# Arbolito.net
KiCad netlist of a schematic drawn in Altium Designer
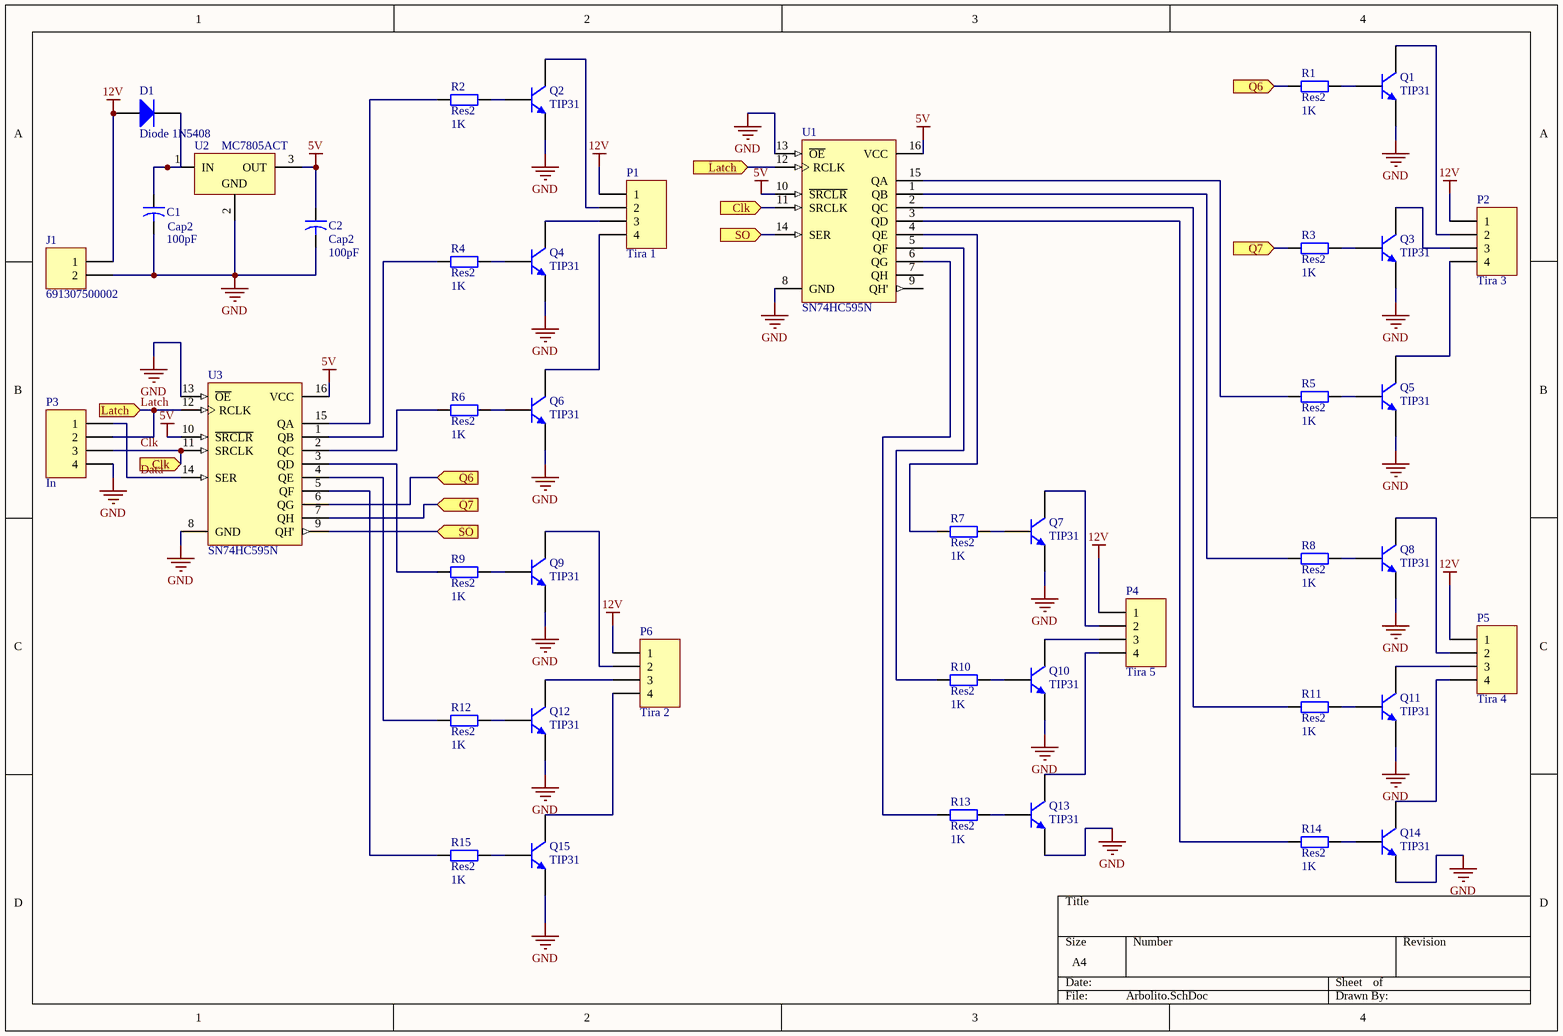
[diagram p0: Arbolito.SchDoc]

(export (version "E")
  (design (tool "Eeschema 10.0.6"))
  (components
    (comp (ref "C1")
      (value "Cap2")
      (footprint "CAPR5-4X5")
      (description "Capacitor")
      (fields (field (name "ALTIUM_VALUE") "100pF") (field (name "PUBLISHER") "Altium Limited"))
      (libsource (lib "Miscellaneous Devices") (part "Cap2"))
    )
    (comp (ref "C2")
      (value "Cap2")
      (footprint "CAPR5-4X5")
      (description "Capacitor")
      (fields (field (name "ALTIUM_VALUE") "100pF") (field (name "PUBLISHER") "Altium Limited"))
      (libsource (lib "Miscellaneous Devices") (part "Cap2"))
    )
    (comp (ref "D1")
      (value "Diode 1N5408")
      (footprint "DO-201AD")
      (description "3 Amp Medium Power Silicon Rectifier Diode")
      (fields (field (name "PUBLISHER") "Altium Limited"))
      (libsource (lib "Miscellaneous Devices") (part "Diode 1N5408"))
    )
    (comp (ref "J1")
      (value "691307500002")
      (footprint "691307500002")
      (description "WR-TBL Terminal block - serie 3075")
      (fields
        (field (name "MANUFACTURER") "Würth Elektronik eiSos GmbH")
        (field (name "CREATED BY") "Karrer Zheng")
      )
      (libsource (lib "WE_WR-TBL_Pluggable System_5.08 mm_rev15b") (part "691307500002"))
    )
    (comp (ref "P1")
      (value "Tira 1")
      (footprint "HDR1X4")
      (description "Header, 4-Pin")
      (fields (field (name "PUBLISHER") "Altium Limited"))
      (libsource (lib "Miscellaneous Connectors") (part "Header 4"))
    )
    (comp (ref "P2")
      (value "Tira 3")
      (footprint "HDR1X4")
      (description "Header, 4-Pin")
      (fields (field (name "PUBLISHER") "Altium Limited"))
      (libsource (lib "Miscellaneous Connectors") (part "Header 4"))
    )
    (comp (ref "P3")
      (value "In")
      (footprint "HDR1X4")
      (description "Header, 4-Pin")
      (fields (field (name "PUBLISHER") "Altium Limited"))
      (libsource (lib "") (part "Header 4_1"))
    )
    (comp (ref "P4")
      (value "Tira 5")
      (footprint "HDR1X4")
      (description "Header, 4-Pin")
      (fields (field (name "PUBLISHER") "Altium Limited"))
      (libsource (lib "Miscellaneous Connectors") (part "Header 4"))
    )
    (comp (ref "P5")
      (value "Tira 4")
      (footprint "HDR1X4")
      (description "Header, 4-Pin")
      (fields (field (name "PUBLISHER") "Altium Limited"))
      (libsource (lib "Miscellaneous Connectors") (part "Header 4"))
    )
    (comp (ref "P6")
      (value "Tira 2")
      (footprint "HDR1X4")
      (description "Header, 4-Pin")
      (fields (field (name "PUBLISHER") "Altium Limited"))
      (libsource (lib "Miscellaneous Connectors") (part "Header 4"))
    )
    (comp (ref "Q1")
      (value "TIP31")
      (footprint "TO-220-AB")
      (description "NPN General Purpose Amplifier")
      (fields (field (name "PUBLISHER") "Altium Limited"))
      (libsource (lib "Miscellaneous Devices") (part "2N3904"))
    )
    (comp (ref "Q2")
      (value "TIP31")
      (footprint "TO-220-AB")
      (description "NPN General Purpose Amplifier")
      (fields (field (name "PUBLISHER") "Altium Limited"))
      (libsource (lib "Miscellaneous Devices") (part "2N3904"))
    )
    (comp (ref "Q3")
      (value "TIP31")
      (footprint "TO-220-AB")
      (description "NPN General Purpose Amplifier")
      (fields (field (name "PUBLISHER") "Altium Limited"))
      (libsource (lib "Miscellaneous Devices") (part "2N3904"))
    )
    (comp (ref "Q4")
      (value "TIP31")
      (footprint "TO-220-AB")
      (description "NPN General Purpose Amplifier")
      (fields (field (name "PUBLISHER") "Altium Limited"))
      (libsource (lib "Miscellaneous Devices") (part "2N3904"))
    )
    (comp (ref "Q5")
      (value "TIP31")
      (footprint "TO-220-AB")
      (description "NPN General Purpose Amplifier")
      (fields (field (name "PUBLISHER") "Altium Limited"))
      (libsource (lib "Miscellaneous Devices") (part "2N3904"))
    )
    (comp (ref "Q6")
      (value "TIP31")
      (footprint "TO-220-AB")
      (description "NPN General Purpose Amplifier")
      (fields (field (name "PUBLISHER") "Altium Limited"))
      (libsource (lib "Miscellaneous Devices") (part "2N3904"))
    )
    (comp (ref "Q7")
      (value "TIP31")
      (footprint "TO-220-AB")
      (description "NPN General Purpose Amplifier")
      (fields (field (name "PUBLISHER") "Altium Limited"))
      (libsource (lib "Miscellaneous Devices") (part "2N3904"))
    )
    (comp (ref "Q8")
      (value "TIP31")
      (footprint "TO-220-AB")
      (description "NPN General Purpose Amplifier")
      (fields (field (name "PUBLISHER") "Altium Limited"))
      (libsource (lib "Miscellaneous Devices") (part "2N3904"))
    )
    (comp (ref "Q9")
      (value "TIP31")
      (footprint "TO-220-AB")
      (description "NPN General Purpose Amplifier")
      (fields (field (name "PUBLISHER") "Altium Limited"))
      (libsource (lib "Miscellaneous Devices") (part "2N3904"))
    )
    (comp (ref "Q10")
      (value "TIP31")
      (footprint "TO-220-AB")
      (description "NPN General Purpose Amplifier")
      (fields (field (name "PUBLISHER") "Altium Limited"))
      (libsource (lib "Miscellaneous Devices") (part "2N3904"))
    )
    (comp (ref "Q11")
      (value "TIP31")
      (footprint "TO-220-AB")
      (description "NPN General Purpose Amplifier")
      (fields (field (name "PUBLISHER") "Altium Limited"))
      (libsource (lib "Miscellaneous Devices") (part "2N3904"))
    )
    (comp (ref "Q12")
      (value "TIP31")
      (footprint "TO-220-AB")
      (description "NPN General Purpose Amplifier")
      (fields (field (name "PUBLISHER") "Altium Limited"))
      (libsource (lib "Miscellaneous Devices") (part "2N3904"))
    )
    (comp (ref "Q13")
      (value "TIP31")
      (footprint "TO-220-AB")
      (description "NPN General Purpose Amplifier")
      (fields (field (name "PUBLISHER") "Altium Limited"))
      (libsource (lib "Miscellaneous Devices") (part "2N3904"))
    )
    (comp (ref "Q14")
      (value "TIP31")
      (footprint "TO-220-AB")
      (description "NPN General Purpose Amplifier")
      (fields (field (name "PUBLISHER") "Altium Limited"))
      (libsource (lib "Miscellaneous Devices") (part "2N3904"))
    )
    (comp (ref "Q15")
      (value "TIP31")
      (footprint "TO-220-AB")
      (description "NPN General Purpose Amplifier")
      (fields (field (name "PUBLISHER") "Altium Limited"))
      (libsource (lib "Miscellaneous Devices") (part "2N3904"))
    )
    (comp (ref "R1")
      (value "Res2")
      (footprint "AXIAL-0.4")
      (description "Resistor")
      (fields (field (name "ALTIUM_VALUE") "1K") (field (name "PUBLISHER") "Altium Limited"))
      (libsource (lib "Miscellaneous Devices") (part "Res2"))
    )
    (comp (ref "R2")
      (value "Res2")
      (footprint "AXIAL-0.4")
      (description "Resistor")
      (fields (field (name "ALTIUM_VALUE") "1K") (field (name "PUBLISHER") "Altium Limited"))
      (libsource (lib "Miscellaneous Devices") (part "Res2"))
    )
    (comp (ref "R3")
      (value "Res2")
      (footprint "AXIAL-0.4")
      (description "Resistor")
      (fields (field (name "ALTIUM_VALUE") "1K") (field (name "PUBLISHER") "Altium Limited"))
      (libsource (lib "Miscellaneous Devices") (part "Res2"))
    )
    (comp (ref "R4")
      (value "Res2")
      (footprint "AXIAL-0.4")
      (description "Resistor")
      (fields (field (name "ALTIUM_VALUE") "1K") (field (name "PUBLISHER") "Altium Limited"))
      (libsource (lib "Miscellaneous Devices") (part "Res2"))
    )
    (comp (ref "R5")
      (value "Res2")
      (footprint "AXIAL-0.4")
      (description "Resistor")
      (fields (field (name "ALTIUM_VALUE") "1K") (field (name "PUBLISHER") "Altium Limited"))
      (libsource (lib "Miscellaneous Devices") (part "Res2"))
    )
    (comp (ref "R6")
      (value "Res2")
      (footprint "AXIAL-0.4")
      (description "Resistor")
      (fields (field (name "ALTIUM_VALUE") "1K") (field (name "PUBLISHER") "Altium Limited"))
      (libsource (lib "Miscellaneous Devices") (part "Res2"))
    )
    (comp (ref "R7")
      (value "Res2")
      (footprint "AXIAL-0.4")
      (description "Resistor")
      (fields (field (name "ALTIUM_VALUE") "1K") (field (name "PUBLISHER") "Altium Limited"))
      (libsource (lib "Miscellaneous Devices") (part "Res2"))
    )
    (comp (ref "R8")
      (value "Res2")
      (footprint "AXIAL-0.4")
      (description "Resistor")
      (fields (field (name "ALTIUM_VALUE") "1K") (field (name "PUBLISHER") "Altium Limited"))
      (libsource (lib "Miscellaneous Devices") (part "Res2"))
    )
    (comp (ref "R9")
      (value "Res2")
      (footprint "AXIAL-0.4")
      (description "Resistor")
      (fields (field (name "ALTIUM_VALUE") "1K") (field (name "PUBLISHER") "Altium Limited"))
      (libsource (lib "Miscellaneous Devices") (part "Res2"))
    )
    (comp (ref "R10")
      (value "Res2")
      (footprint "AXIAL-0.4")
      (description "Resistor")
      (fields (field (name "ALTIUM_VALUE") "1K") (field (name "PUBLISHER") "Altium Limited"))
      (libsource (lib "Miscellaneous Devices") (part "Res2"))
    )
    (comp (ref "R11")
      (value "Res2")
      (footprint "AXIAL-0.4")
      (description "Resistor")
      (fields (field (name "ALTIUM_VALUE") "1K") (field (name "PUBLISHER") "Altium Limited"))
      (libsource (lib "Miscellaneous Devices") (part "Res2"))
    )
    (comp (ref "R12")
      (value "Res2")
      (footprint "AXIAL-0.4")
      (description "Resistor")
      (fields (field (name "ALTIUM_VALUE") "1K") (field (name "PUBLISHER") "Altium Limited"))
      (libsource (lib "Miscellaneous Devices") (part "Res2"))
    )
    (comp (ref "R13")
      (value "Res2")
      (footprint "AXIAL-0.4")
      (description "Resistor")
      (fields (field (name "ALTIUM_VALUE") "1K") (field (name "PUBLISHER") "Altium Limited"))
      (libsource (lib "Miscellaneous Devices") (part "Res2"))
    )
    (comp (ref "R14")
      (value "Res2")
      (footprint "AXIAL-0.4")
      (description "Resistor")
      (fields (field (name "ALTIUM_VALUE") "1K") (field (name "PUBLISHER") "Altium Limited"))
      (libsource (lib "Miscellaneous Devices") (part "Res2"))
    )
    (comp (ref "R15")
      (value "Res2")
      (footprint "AXIAL-0.4")
      (description "Resistor")
      (fields (field (name "ALTIUM_VALUE") "1K") (field (name "PUBLISHER") "Altium Limited"))
      (libsource (lib "Miscellaneous Devices") (part "Res2"))
    )
    (comp (ref "U1")
      (value "SN74HC595N")
      (footprint "N016")
      (description "8-Bit Shift Register with 3-State Output Registers")
      (fields (field (name "PUBLISHER") "Altium Limited"))
      (libsource (lib "TI Logic Register") (part "SN74HC595N"))
    )
    (comp (ref "U2")
      (value "MC7805ACT")
      (footprint "221A-04")
      (description "3-Terminal Positive Fixed Voltage Regulator")
      (fields (field (name "PUBLISHER") "Altium Limited"))
      (libsource (lib "Motorola Power Mgt Voltage Regulator") (part "MC7805ACT"))
    )
    (comp (ref "U3")
      (value "SN74HC595N")
      (footprint "N016")
      (description "8-Bit Shift Register with 3-State Output Registers")
      (fields (field (name "PUBLISHER") "Altium Limited"))
      (libsource (lib "TI Logic Register") (part "SN74HC595N"))
    )
  )
  (nets
    (net (code "1") (name "/Clk") (class "Default")
      (node (ref "P3") (pin "3") (pinfunction "3_3") (pintype "passive"))
      (node (ref "U1") (pin "11") (pinfunction "SRCLK_11") (pintype "input"))
      (node (ref "U3") (pin "11") (pinfunction "SRCLK_11") (pintype "input"))
    )
    (net (code "2") (name "/Data") (class "Default")
      (node (ref "P3") (pin "1") (pinfunction "1_1") (pintype "passive"))
      (node (ref "U3") (pin "14") (pinfunction "SER_14") (pintype "input"))
    )
    (net (code "3") (name "/Latch") (class "Default")
      (node (ref "P3") (pin "2") (pinfunction "2_2") (pintype "passive"))
      (node (ref "U1") (pin "12") (pinfunction "RCLK_12") (pintype "input"))
      (node (ref "U3") (pin "12") (pinfunction "RCLK_12") (pintype "input"))
    )
    (net (code "4") (name "/Q6") (class "Default")
      (node (ref "R1") (pin "1") (pinfunction "1_1") (pintype "passive"))
      (node (ref "U3") (pin "6") (pinfunction "QG_6") (pintype "tri_state"))
    )
    (net (code "5") (name "/Q7") (class "Default")
      (node (ref "R3") (pin "1") (pinfunction "1_1") (pintype "passive"))
      (node (ref "U3") (pin "7") (pinfunction "QH_7") (pintype "tri_state"))
    )
    (net (code "6") (name "/SO") (class "Default")
      (node (ref "U1") (pin "14") (pinfunction "SER_14") (pintype "input"))
      (node (ref "U3") (pin "9") (pinfunction "QH'_9") (pintype "output"))
    )
    (net (code "7") (name "5V") (class "Default")
      (node (ref "C2") (pin "1") (pinfunction "1_1") (pintype "passive"))
      (node (ref "U1") (pin "10") (pinfunction "~{SRCLR}_10") (pintype "input"))
      (node (ref "U1") (pin "16") (pinfunction "VCC_16") (pintype "power_in"))
      (node (ref "U2") (pin "3") (pinfunction "OUT_3") (pintype "power_in"))
      (node (ref "U3") (pin "10") (pinfunction "~{SRCLR}_10") (pintype "input"))
      (node (ref "U3") (pin "16") (pinfunction "VCC_16") (pintype "power_in"))
    )
    (net (code "8") (name "12V") (class "Default")
      (node (ref "D1") (pin "1") (pinfunction "A_1") (pintype "passive"))
      (node (ref "J1") (pin "1") (pinfunction "1_1") (pintype "passive"))
      (node (ref "P1") (pin "1") (pinfunction "1_1") (pintype "passive"))
      (node (ref "P2") (pin "1") (pinfunction "1_1") (pintype "passive"))
      (node (ref "P4") (pin "1") (pinfunction "1_1") (pintype "passive"))
      (node (ref "P5") (pin "1") (pinfunction "1_1") (pintype "passive"))
      (node (ref "P6") (pin "1") (pinfunction "1_1") (pintype "passive"))
    )
    (net (code "9") (name "GND") (class "Default")
      (node (ref "C1") (pin "2") (pinfunction "2_2") (pintype "passive"))
      (node (ref "C2") (pin "2") (pinfunction "2_2") (pintype "passive"))
      (node (ref "J1") (pin "2") (pinfunction "2_2") (pintype "passive"))
      (node (ref "P3") (pin "4") (pinfunction "4_4") (pintype "passive"))
      (node (ref "Q1") (pin "1") (pinfunction "E_1") (pintype "passive"))
      (node (ref "Q10") (pin "1") (pinfunction "E_1") (pintype "passive"))
      (node (ref "Q11") (pin "1") (pinfunction "E_1") (pintype "passive"))
      (node (ref "Q12") (pin "1") (pinfunction "E_1") (pintype "passive"))
      (node (ref "Q13") (pin "1") (pinfunction "E_1") (pintype "passive"))
      (node (ref "Q14") (pin "1") (pinfunction "E_1") (pintype "passive"))
      (node (ref "Q15") (pin "1") (pinfunction "E_1") (pintype "passive"))
      (node (ref "Q2") (pin "1") (pinfunction "E_1") (pintype "passive"))
      (node (ref "Q3") (pin "1") (pinfunction "E_1") (pintype "passive"))
      (node (ref "Q4") (pin "1") (pinfunction "E_1") (pintype "passive"))
      (node (ref "Q5") (pin "1") (pinfunction "E_1") (pintype "passive"))
      (node (ref "Q6") (pin "1") (pinfunction "E_1") (pintype "passive"))
      (node (ref "Q7") (pin "1") (pinfunction "E_1") (pintype "passive"))
      (node (ref "Q8") (pin "1") (pinfunction "E_1") (pintype "passive"))
      (node (ref "Q9") (pin "1") (pinfunction "E_1") (pintype "passive"))
      (node (ref "U1") (pin "13") (pinfunction "~{OE}_13") (pintype "input"))
      (node (ref "U1") (pin "8") (pinfunction "GND_8") (pintype "power_in"))
      (node (ref "U2") (pin "2") (pinfunction "GND_2") (pintype "power_in"))
      (node (ref "U3") (pin "13") (pinfunction "~{OE}_13") (pintype "input"))
      (node (ref "U3") (pin "8") (pinfunction "GND_8") (pintype "power_in"))
    )
    (net (code "10") (name "Net-(D1-K)") (class "Default")
      (node (ref "C1") (pin "1") (pinfunction "1_1") (pintype "passive"))
      (node (ref "D1") (pin "2") (pinfunction "K_2") (pintype "passive"))
      (node (ref "U2") (pin "1") (pinfunction "IN_1") (pintype "power_in"))
    )
    (net (code "11") (name "Net-(Q1-B)") (class "Default")
      (node (ref "Q1") (pin "2") (pinfunction "B_2") (pintype "passive"))
      (node (ref "R1") (pin "2") (pinfunction "2_2") (pintype "passive"))
    )
    (net (code "12") (name "Net-(Q1-C)") (class "Default")
      (node (ref "P2") (pin "2") (pinfunction "2_2") (pintype "passive"))
      (node (ref "Q1") (pin "3") (pinfunction "C_3") (pintype "passive"))
    )
    (net (code "13") (name "Net-(Q2-B)") (class "Default")
      (node (ref "Q2") (pin "2") (pinfunction "B_2") (pintype "passive"))
      (node (ref "R2") (pin "2") (pinfunction "2_2") (pintype "passive"))
    )
    (net (code "14") (name "Net-(Q2-C)") (class "Default")
      (node (ref "P1") (pin "2") (pinfunction "2_2") (pintype "passive"))
      (node (ref "Q2") (pin "3") (pinfunction "C_3") (pintype "passive"))
    )
    (net (code "15") (name "Net-(Q3-B)") (class "Default")
      (node (ref "Q3") (pin "2") (pinfunction "B_2") (pintype "passive"))
      (node (ref "R3") (pin "2") (pinfunction "2_2") (pintype "passive"))
    )
    (net (code "16") (name "Net-(Q3-C)") (class "Default")
      (node (ref "P2") (pin "3") (pinfunction "3_3") (pintype "passive"))
      (node (ref "Q3") (pin "3") (pinfunction "C_3") (pintype "passive"))
    )
    (net (code "17") (name "Net-(Q4-B)") (class "Default")
      (node (ref "Q4") (pin "2") (pinfunction "B_2") (pintype "passive"))
      (node (ref "R4") (pin "2") (pinfunction "2_2") (pintype "passive"))
    )
    (net (code "18") (name "Net-(Q4-C)") (class "Default")
      (node (ref "P1") (pin "3") (pinfunction "3_3") (pintype "passive"))
      (node (ref "Q4") (pin "3") (pinfunction "C_3") (pintype "passive"))
    )
    (net (code "19") (name "Net-(Q5-B)") (class "Default")
      (node (ref "Q5") (pin "2") (pinfunction "B_2") (pintype "passive"))
      (node (ref "R5") (pin "2") (pinfunction "2_2") (pintype "passive"))
    )
    (net (code "20") (name "Net-(Q5-C)") (class "Default")
      (node (ref "P2") (pin "4") (pinfunction "4_4") (pintype "passive"))
      (node (ref "Q5") (pin "3") (pinfunction "C_3") (pintype "passive"))
    )
    (net (code "21") (name "Net-(Q6-B)") (class "Default")
      (node (ref "Q6") (pin "2") (pinfunction "B_2") (pintype "passive"))
      (node (ref "R6") (pin "2") (pinfunction "2_2") (pintype "passive"))
    )
    (net (code "22") (name "Net-(Q6-C)") (class "Default")
      (node (ref "P1") (pin "4") (pinfunction "4_4") (pintype "passive"))
      (node (ref "Q6") (pin "3") (pinfunction "C_3") (pintype "passive"))
    )
    (net (code "23") (name "Net-(Q7-B)") (class "Default")
      (node (ref "Q7") (pin "2") (pinfunction "B_2") (pintype "passive"))
      (node (ref "R7") (pin "2") (pinfunction "2_2") (pintype "passive"))
    )
    (net (code "24") (name "Net-(Q7-C)") (class "Default")
      (node (ref "P4") (pin "2") (pinfunction "2_2") (pintype "passive"))
      (node (ref "Q7") (pin "3") (pinfunction "C_3") (pintype "passive"))
    )
    (net (code "25") (name "Net-(Q8-B)") (class "Default")
      (node (ref "Q8") (pin "2") (pinfunction "B_2") (pintype "passive"))
      (node (ref "R8") (pin "2") (pinfunction "2_2") (pintype "passive"))
    )
    (net (code "26") (name "Net-(Q8-C)") (class "Default")
      (node (ref "P5") (pin "2") (pinfunction "2_2") (pintype "passive"))
      (node (ref "Q8") (pin "3") (pinfunction "C_3") (pintype "passive"))
    )
    (net (code "27") (name "Net-(Q9-B)") (class "Default")
      (node (ref "Q9") (pin "2") (pinfunction "B_2") (pintype "passive"))
      (node (ref "R9") (pin "2") (pinfunction "2_2") (pintype "passive"))
    )
    (net (code "28") (name "Net-(Q9-C)") (class "Default")
      (node (ref "P6") (pin "2") (pinfunction "2_2") (pintype "passive"))
      (node (ref "Q9") (pin "3") (pinfunction "C_3") (pintype "passive"))
    )
    (net (code "29") (name "Net-(Q10-B)") (class "Default")
      (node (ref "Q10") (pin "2") (pinfunction "B_2") (pintype "passive"))
      (node (ref "R10") (pin "2") (pinfunction "2_2") (pintype "passive"))
    )
    (net (code "30") (name "Net-(Q10-C)") (class "Default")
      (node (ref "P4") (pin "3") (pinfunction "3_3") (pintype "passive"))
      (node (ref "Q10") (pin "3") (pinfunction "C_3") (pintype "passive"))
    )
    (net (code "31") (name "Net-(Q11-B)") (class "Default")
      (node (ref "Q11") (pin "2") (pinfunction "B_2") (pintype "passive"))
      (node (ref "R11") (pin "2") (pinfunction "2_2") (pintype "passive"))
    )
    (net (code "32") (name "Net-(Q11-C)") (class "Default")
      (node (ref "P5") (pin "3") (pinfunction "3_3") (pintype "passive"))
      (node (ref "Q11") (pin "3") (pinfunction "C_3") (pintype "passive"))
    )
    (net (code "33") (name "Net-(Q12-B)") (class "Default")
      (node (ref "Q12") (pin "2") (pinfunction "B_2") (pintype "passive"))
      (node (ref "R12") (pin "2") (pinfunction "2_2") (pintype "passive"))
    )
    (net (code "34") (name "Net-(Q12-C)") (class "Default")
      (node (ref "P6") (pin "3") (pinfunction "3_3") (pintype "passive"))
      (node (ref "Q12") (pin "3") (pinfunction "C_3") (pintype "passive"))
    )
    (net (code "35") (name "Net-(Q13-B)") (class "Default")
      (node (ref "Q13") (pin "2") (pinfunction "B_2") (pintype "passive"))
      (node (ref "R13") (pin "2") (pinfunction "2_2") (pintype "passive"))
    )
    (net (code "36") (name "Net-(Q13-C)") (class "Default")
      (node (ref "P4") (pin "4") (pinfunction "4_4") (pintype "passive"))
      (node (ref "Q13") (pin "3") (pinfunction "C_3") (pintype "passive"))
    )
    (net (code "37") (name "Net-(Q14-B)") (class "Default")
      (node (ref "Q14") (pin "2") (pinfunction "B_2") (pintype "passive"))
      (node (ref "R14") (pin "2") (pinfunction "2_2") (pintype "passive"))
    )
    (net (code "38") (name "Net-(Q14-C)") (class "Default")
      (node (ref "P5") (pin "4") (pinfunction "4_4") (pintype "passive"))
      (node (ref "Q14") (pin "3") (pinfunction "C_3") (pintype "passive"))
    )
    (net (code "39") (name "Net-(Q15-B)") (class "Default")
      (node (ref "Q15") (pin "2") (pinfunction "B_2") (pintype "passive"))
      (node (ref "R15") (pin "2") (pinfunction "2_2") (pintype "passive"))
    )
    (net (code "40") (name "Net-(Q15-C)") (class "Default")
      (node (ref "P6") (pin "4") (pinfunction "4_4") (pintype "passive"))
      (node (ref "Q15") (pin "3") (pinfunction "C_3") (pintype "passive"))
    )
    (net (code "41") (name "Net-(U1-QA)") (class "Default")
      (node (ref "R5") (pin "1") (pinfunction "1_1") (pintype "passive"))
      (node (ref "U1") (pin "15") (pinfunction "QA_15") (pintype "tri_state"))
    )
    (net (code "42") (name "Net-(U1-QB)") (class "Default")
      (node (ref "R8") (pin "1") (pinfunction "1_1") (pintype "passive"))
      (node (ref "U1") (pin "1") (pinfunction "QB_1") (pintype "tri_state"))
    )
    (net (code "43") (name "Net-(U1-QC)") (class "Default")
      (node (ref "R11") (pin "1") (pinfunction "1_1") (pintype "passive"))
      (node (ref "U1") (pin "2") (pinfunction "QC_2") (pintype "tri_state"))
    )
    (net (code "44") (name "Net-(U1-QD)") (class "Default")
      (node (ref "R14") (pin "1") (pinfunction "1_1") (pintype "passive"))
      (node (ref "U1") (pin "3") (pinfunction "QD_3") (pintype "tri_state"))
    )
    (net (code "45") (name "Net-(U1-QE)") (class "Default")
      (node (ref "R7") (pin "1") (pinfunction "1_1") (pintype "passive"))
      (node (ref "U1") (pin "4") (pinfunction "QE_4") (pintype "tri_state"))
    )
    (net (code "46") (name "Net-(U1-QF)") (class "Default")
      (node (ref "R10") (pin "1") (pinfunction "1_1") (pintype "passive"))
      (node (ref "U1") (pin "5") (pinfunction "QF_5") (pintype "tri_state"))
    )
    (net (code "47") (name "Net-(U1-QG)") (class "Default")
      (node (ref "R13") (pin "1") (pinfunction "1_1") (pintype "passive"))
      (node (ref "U1") (pin "6") (pinfunction "QG_6") (pintype "tri_state"))
    )
    (net (code "48") (name "Net-(U3-QA)") (class "Default")
      (node (ref "R2") (pin "1") (pinfunction "1_1") (pintype "passive"))
      (node (ref "U3") (pin "15") (pinfunction "QA_15") (pintype "tri_state"))
    )
    (net (code "49") (name "Net-(U3-QB)") (class "Default")
      (node (ref "R4") (pin "1") (pinfunction "1_1") (pintype "passive"))
      (node (ref "U3") (pin "1") (pinfunction "QB_1") (pintype "tri_state"))
    )
    (net (code "50") (name "Net-(U3-QC)") (class "Default")
      (node (ref "R6") (pin "1") (pinfunction "1_1") (pintype "passive"))
      (node (ref "U3") (pin "2") (pinfunction "QC_2") (pintype "tri_state"))
    )
    (net (code "51") (name "Net-(U3-QD)") (class "Default")
      (node (ref "R9") (pin "1") (pinfunction "1_1") (pintype "passive"))
      (node (ref "U3") (pin "3") (pinfunction "QD_3") (pintype "tri_state"))
    )
    (net (code "52") (name "Net-(U3-QE)") (class "Default")
      (node (ref "R12") (pin "1") (pinfunction "1_1") (pintype "passive"))
      (node (ref "U3") (pin "4") (pinfunction "QE_4") (pintype "tri_state"))
    )
    (net (code "53") (name "Net-(U3-QF)") (class "Default")
      (node (ref "R15") (pin "1") (pinfunction "1_1") (pintype "passive"))
      (node (ref "U3") (pin "5") (pinfunction "QF_5") (pintype "tri_state"))
    )
    (net (code "54") (name "unconnected-(U1-QH'-Pad9)") (class "Default")
      (node (ref "U1") (pin "9") (pinfunction "QH'_9") (pintype "output"))
    )
    (net (code "55") (name "unconnected-(U1-QH-Pad7)") (class "Default")
      (node (ref "U1") (pin "7") (pinfunction "QH_7") (pintype "tri_state"))
    )
  )
)
